# ADE7758.net
KiCad netlist of a schematic drawn in EAGLE
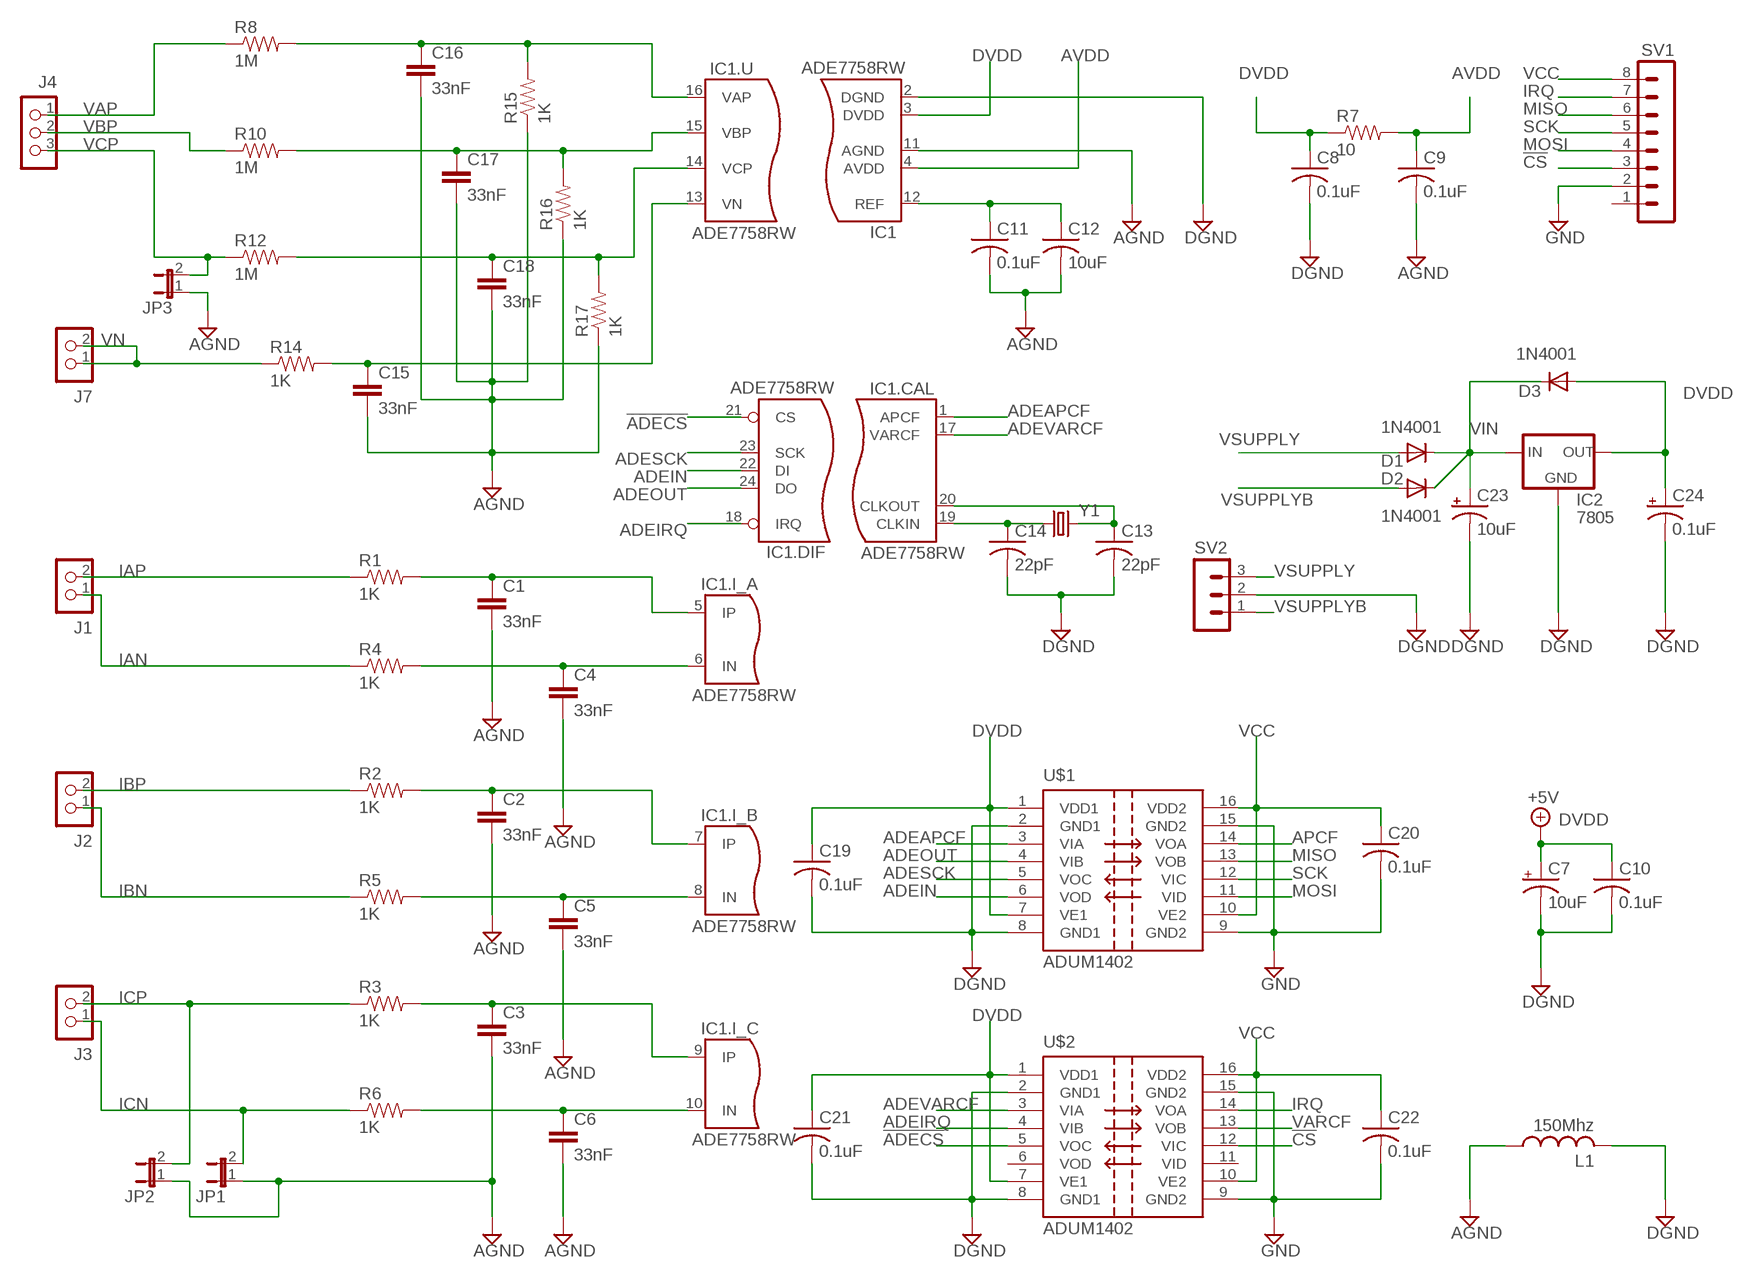
[diagram p0: schematic, sheet 1]

(export (version "E")
  (design (tool "Eeschema 10.0.6"))
  (components
    (comp (ref "C1")
      (value "33nF")
      (footprint "eagle-import:CAP-PTH-SMALL2")
      (libsource (lib "eagle-import") (part "CAPPTH2"))
    )
    (comp (ref "C2")
      (value "33nF")
      (footprint "eagle-import:CAP-PTH-SMALL2")
      (libsource (lib "eagle-import") (part "CAPPTH2"))
    )
    (comp (ref "C3")
      (value "33nF")
      (footprint "eagle-import:CAP-PTH-SMALL2")
      (libsource (lib "eagle-import") (part "CAPPTH2"))
    )
    (comp (ref "C4")
      (value "33nF")
      (footprint "eagle-import:CAP-PTH-SMALL2")
      (libsource (lib "eagle-import") (part "CAPPTH2"))
    )
    (comp (ref "C5")
      (value "33nF")
      (footprint "eagle-import:CAP-PTH-SMALL2")
      (libsource (lib "eagle-import") (part "CAPPTH2"))
    )
    (comp (ref "C6")
      (value "33nF")
      (footprint "eagle-import:CAP-PTH-SMALL2")
      (libsource (lib "eagle-import") (part "CAPPTH2"))
    )
    (comp (ref "C7")
      (value "10uF")
      (footprint "eagle-import:C_6032-28R")
      (libsource (lib "eagle-import") (part "CPOL-USC/6032-28R"))
    )
    (comp (ref "C8")
      (value "0.1uF")
      (footprint "eagle-import:C0805")
      (libsource (lib "eagle-import") (part "C-USC0805"))
    )
    (comp (ref "C9")
      (value "0.1uF")
      (footprint "eagle-import:C0805")
      (libsource (lib "eagle-import") (part "C-USC0805"))
    )
    (comp (ref "C10")
      (value "0.1uF")
      (footprint "eagle-import:C0805")
      (libsource (lib "eagle-import") (part "C-USC0805"))
    )
    (comp (ref "C11")
      (value "0.1uF")
      (footprint "eagle-import:C0805K")
      (libsource (lib "eagle-import") (part "C-USC0805K"))
    )
    (comp (ref "C12")
      (value "10uF")
      (footprint "eagle-import:C0805K")
      (libsource (lib "eagle-import") (part "C-USC0805K"))
    )
    (comp (ref "C13")
      (value "22pF")
      (footprint "eagle-import:C0805K")
      (libsource (lib "eagle-import") (part "C-USC0805K"))
    )
    (comp (ref "C14")
      (value "22pF")
      (footprint "eagle-import:C0805K")
      (libsource (lib "eagle-import") (part "C-USC0805K"))
    )
    (comp (ref "C15")
      (value "33nF")
      (footprint "eagle-import:CAP-PTH-SMALL2")
      (libsource (lib "eagle-import") (part "CAPPTH2"))
    )
    (comp (ref "C16")
      (value "33nF")
      (footprint "eagle-import:CAP-PTH-SMALL2")
      (libsource (lib "eagle-import") (part "CAPPTH2"))
    )
    (comp (ref "C17")
      (value "33nF")
      (footprint "eagle-import:CAP-PTH-SMALL2")
      (libsource (lib "eagle-import") (part "CAPPTH2"))
    )
    (comp (ref "C18")
      (value "33nF")
      (footprint "eagle-import:CAP-PTH-SMALL2")
      (libsource (lib "eagle-import") (part "CAPPTH2"))
    )
    (comp (ref "C19")
      (value "0.1uF")
      (footprint "eagle-import:C0805")
      (libsource (lib "eagle-import") (part "C-USC0805"))
    )
    (comp (ref "C20")
      (value "0.1uF")
      (footprint "eagle-import:C0805")
      (libsource (lib "eagle-import") (part "C-USC0805"))
    )
    (comp (ref "C21")
      (value "0.1uF")
      (footprint "eagle-import:C0805")
      (libsource (lib "eagle-import") (part "C-USC0805"))
    )
    (comp (ref "C22")
      (value "0.1uF")
      (footprint "eagle-import:C0805")
      (libsource (lib "eagle-import") (part "C-USC0805"))
    )
    (comp (ref "C23")
      (value "10uF")
      (footprint "eagle-import:CPOL-RADIAL-100UF-25V")
      (fields (field (name "MPN") "06034D106MAT2A"))
      (libsource (lib "eagle-import") (part "CAP_POLPTH1"))
    )
    (comp (ref "C24")
      (value "0.1uF")
      (footprint "eagle-import:CPOL-RADIAL-10UF-25V")
      (fields (field (name "MPN") "06034D106MAT2A"))
      (libsource (lib "eagle-import") (part "CAP_POLPTH2"))
    )
    (comp (ref "D1")
      (value "1N4001")
      (footprint "eagle-import:D-7.5")
      (libsource (lib "eagle-import") (part "DIODE-D-7.5"))
    )
    (comp (ref "D2")
      (value "1N4001")
      (footprint "eagle-import:D-7.5")
      (libsource (lib "eagle-import") (part "DIODE-D-7.5"))
    )
    (comp (ref "D3")
      (value "1N4001")
      (footprint "eagle-import:D-7.5")
      (libsource (lib "eagle-import") (part "DIODE-D-7.5"))
    )
    (comp (ref "IC1")
      (value "ADE7758RW")
      (footprint "eagle-import:SOIC24")
      (libsource (lib "eagle-import") (part "ADE7758RW"))
    )
    (comp (ref "IC2")
      (value "7805")
      (footprint "eagle-import:78XXS")
      (libsource (lib "eagle-import") (part "78XXS"))
    )
    (comp (ref "J1")
      (value "CON_TERMINAL_BLOCK_02-5MM")
      (footprint "eagle-import:TERMINAL_BLOCK_2P_5")
      (libsource (lib "eagle-import") (part "CON_TERMINAL_BLOCK_02-5MM"))
    )
    (comp (ref "J2")
      (value "CON_TERMINAL_BLOCK_02-5MM")
      (footprint "eagle-import:TERMINAL_BLOCK_2P_5")
      (libsource (lib "eagle-import") (part "CON_TERMINAL_BLOCK_02-5MM"))
    )
    (comp (ref "J3")
      (value "CON_TERMINAL_BLOCK_02-5MM")
      (footprint "eagle-import:TERMINAL_BLOCK_2P_5")
      (libsource (lib "eagle-import") (part "CON_TERMINAL_BLOCK_02-5MM"))
    )
    (comp (ref "J4")
      (value "CON_TERMINAL_BLOCK_03-5MM")
      (footprint "eagle-import:TERMINAL_BLOCK_3P_5")
      (libsource (lib "eagle-import") (part "CON_TERMINAL_BLOCK_03-5MM"))
    )
    (comp (ref "J7")
      (value "CON_TERMINAL_BLOCK_02-5MM")
      (footprint "eagle-import:TERMINAL_BLOCK_2P_5")
      (libsource (lib "eagle-import") (part "CON_TERMINAL_BLOCK_02-5MM"))
    )
    (comp (ref "JP1")
      (value "JP1E")
      (footprint "eagle-import:JP1")
      (libsource (lib "eagle-import") (part "JP1E"))
    )
    (comp (ref "JP2")
      (value "JP1E")
      (footprint "eagle-import:JP1")
      (libsource (lib "eagle-import") (part "JP1E"))
    )
    (comp (ref "JP3")
      (value "JP1E")
      (footprint "eagle-import:JP1")
      (libsource (lib "eagle-import") (part "JP1E"))
    )
    (comp (ref "L1")
      (value "150Mhz")
      (footprint "eagle-import:0207_5V")
      (libsource (lib "eagle-import") (part "L-US0207/5V"))
    )
    (comp (ref "R1")
      (value "1K")
      (footprint "eagle-import:AXIAL-0.4")
      (libsource (lib "eagle-import") (part "RESISTORPTH-1/4W"))
    )
    (comp (ref "R2")
      (value "1K")
      (footprint "eagle-import:AXIAL-0.4")
      (libsource (lib "eagle-import") (part "RESISTORPTH-1/4W"))
    )
    (comp (ref "R3")
      (value "1K")
      (footprint "eagle-import:AXIAL-0.4")
      (libsource (lib "eagle-import") (part "RESISTORPTH-1/4W"))
    )
    (comp (ref "R4")
      (value "1K")
      (footprint "eagle-import:AXIAL-0.4")
      (libsource (lib "eagle-import") (part "RESISTORPTH-1/4W"))
    )
    (comp (ref "R5")
      (value "1K")
      (footprint "eagle-import:AXIAL-0.4")
      (libsource (lib "eagle-import") (part "RESISTORPTH-1/4W"))
    )
    (comp (ref "R6")
      (value "1K")
      (footprint "eagle-import:AXIAL-0.4")
      (libsource (lib "eagle-import") (part "RESISTORPTH-1/4W"))
    )
    (comp (ref "R7")
      (value "10")
      (footprint "eagle-import:AXIAL-0.4")
      (libsource (lib "eagle-import") (part "RESISTORPTH-1/4W"))
    )
    (comp (ref "R8")
      (value "1M")
      (footprint "eagle-import:AXIAL-0.4")
      (libsource (lib "eagle-import") (part "RESISTORPTH-1/4W"))
    )
    (comp (ref "R10")
      (value "1M")
      (footprint "eagle-import:AXIAL-0.4")
      (libsource (lib "eagle-import") (part "RESISTORPTH-1/4W"))
    )
    (comp (ref "R12")
      (value "1M")
      (footprint "eagle-import:AXIAL-0.4")
      (libsource (lib "eagle-import") (part "RESISTORPTH-1/4W"))
    )
    (comp (ref "R14")
      (value "1K")
      (footprint "eagle-import:AXIAL-0.4")
      (libsource (lib "eagle-import") (part "RESISTORPTH-1/4W"))
    )
    (comp (ref "R15")
      (value "1K")
      (footprint "eagle-import:AXIAL-0.4")
      (libsource (lib "eagle-import") (part "RESISTORPTH-1/4W"))
    )
    (comp (ref "R16")
      (value "1K")
      (footprint "eagle-import:AXIAL-0.4")
      (libsource (lib "eagle-import") (part "RESISTORPTH-1/4W"))
    )
    (comp (ref "R17")
      (value "1K")
      (footprint "eagle-import:AXIAL-0.4")
      (libsource (lib "eagle-import") (part "RESISTORPTH-1/4W"))
    )
    (comp (ref "SV1")
      (value "MA08-1")
      (footprint "eagle-import:MA08-1")
      (libsource (lib "eagle-import") (part "MA08-1"))
    )
    (comp (ref "SV2")
      (value "MA03-1")
      (footprint "eagle-import:MA03-1")
      (libsource (lib "eagle-import") (part "MA03-1"))
    )
    (comp (ref "U$1")
      (value "ADUM1402")
      (footprint "eagle-import:SO16W")
      (libsource (lib "eagle-import") (part "ADUM1402"))
    )
    (comp (ref "U$2")
      (value "ADUM1402")
      (footprint "eagle-import:SO16W")
      (libsource (lib "eagle-import") (part "ADUM1402"))
    )
    (comp (ref "Y1")
      (value "CRYSTALHC49US")
      (footprint "eagle-import:HC49US")
      (libsource (lib "eagle-import") (part "CRYSTALHC49US"))
    )
  )
  (nets
    (net (code "1") (name "+5V") (class "Default")
      (node (ref "C10") (pin "1") (pinfunction "1_1") (pintype "passive"))
      (node (ref "C19") (pin "1") (pinfunction "1_1") (pintype "passive"))
      (node (ref "C21") (pin "1") (pinfunction "1_1") (pintype "passive"))
      (node (ref "C24") (pin "1") (pinfunction "+_1") (pintype "passive"))
      (node (ref "C7") (pin "+") (pinfunction "+_+") (pintype "passive"))
      (node (ref "C8") (pin "1") (pinfunction "1_1") (pintype "passive"))
      (node (ref "D3") (pin "A") (pinfunction "A_A") (pintype "passive"))
      (node (ref "IC1") (pin "3") (pinfunction "DVDD_3") (pintype "power_in"))
      (node (ref "IC2") (pin "OUT") (pinfunction "OUT_OUT") (pintype "passive"))
      (node (ref "R7") (pin "P$1") (pinfunction "1_P$1") (pintype "passive"))
      (node (ref "U$1") (pin "1") (pinfunction "VDD1_1") (pintype "power_in"))
      (node (ref "U$1") (pin "7") (pinfunction "VE1_7") (pintype "passive"))
      (node (ref "U$2") (pin "1") (pinfunction "VDD1_1") (pintype "power_in"))
      (node (ref "U$2") (pin "7") (pinfunction "VE1_7") (pintype "passive"))
    )
    (net (code "2") (name "/ADEAPCF") (class "Default")
      (node (ref "IC1") (pin "1") (pinfunction "APCF_1") (pintype "output"))
      (node (ref "U$1") (pin "3") (pinfunction "VIA_3") (pintype "input"))
    )
    (net (code "3") (name "/ADEIN") (class "Default")
      (node (ref "IC1") (pin "22") (pinfunction "DI_22") (pintype "input"))
      (node (ref "U$1") (pin "6") (pinfunction "VOD_6") (pintype "output"))
    )
    (net (code "4") (name "/ADEIRQ") (class "Default")
      (node (ref "IC1") (pin "18") (pinfunction "IRQ_18") (pintype "output"))
      (node (ref "U$2") (pin "4") (pinfunction "VIB_4") (pintype "input"))
    )
    (net (code "5") (name "/ADEOUT") (class "Default")
      (node (ref "IC1") (pin "24") (pinfunction "DO_24") (pintype "output"))
      (node (ref "U$1") (pin "4") (pinfunction "VIB_4") (pintype "input"))
    )
    (net (code "6") (name "/ADESCK") (class "Default")
      (node (ref "IC1") (pin "23") (pinfunction "SCK_23") (pintype "input"))
      (node (ref "U$1") (pin "5") (pinfunction "VOC_5") (pintype "output"))
    )
    (net (code "7") (name "/ADEVARCF") (class "Default")
      (node (ref "IC1") (pin "17") (pinfunction "VARCF_17") (pintype "output"))
      (node (ref "U$2") (pin "3") (pinfunction "VIA_3") (pintype "input"))
    )
    (net (code "8") (name "/APCF") (class "Default")
      (node (ref "U$1") (pin "14") (pinfunction "VOA_14") (pintype "output"))
    )
    (net (code "9") (name "/AVDD") (class "Default")
      (node (ref "C9") (pin "1") (pinfunction "1_1") (pintype "passive"))
      (node (ref "IC1") (pin "4") (pinfunction "AVDD_4") (pintype "power_in"))
      (node (ref "R7") (pin "P$2") (pinfunction "2_P$2") (pintype "passive"))
    )
    (net (code "10") (name "/IAN") (class "Default")
      (node (ref "J1") (pin "1") (pinfunction "1_1") (pintype "passive"))
      (node (ref "R4") (pin "P$1") (pinfunction "1_P$1") (pintype "passive"))
    )
    (net (code "11") (name "/IAP") (class "Default")
      (node (ref "J1") (pin "2") (pinfunction "2_2") (pintype "passive"))
      (node (ref "R1") (pin "P$1") (pinfunction "1_P$1") (pintype "passive"))
    )
    (net (code "12") (name "/IBN") (class "Default")
      (node (ref "J2") (pin "1") (pinfunction "1_1") (pintype "passive"))
      (node (ref "R5") (pin "P$1") (pinfunction "1_P$1") (pintype "passive"))
    )
    (net (code "13") (name "/IBP") (class "Default")
      (node (ref "J2") (pin "2") (pinfunction "2_2") (pintype "passive"))
      (node (ref "R2") (pin "P$1") (pinfunction "1_P$1") (pintype "passive"))
    )
    (net (code "14") (name "/ICN") (class "Default")
      (node (ref "J3") (pin "1") (pinfunction "1_1") (pintype "passive"))
      (node (ref "JP1") (pin "2") (pinfunction "2_2") (pintype "passive"))
      (node (ref "R6") (pin "P$1") (pinfunction "1_P$1") (pintype "passive"))
    )
    (net (code "15") (name "/ICP") (class "Default")
      (node (ref "J3") (pin "2") (pinfunction "2_2") (pintype "passive"))
      (node (ref "JP2") (pin "2") (pinfunction "2_2") (pintype "passive"))
      (node (ref "R3") (pin "P$1") (pinfunction "1_P$1") (pintype "passive"))
    )
    (net (code "16") (name "/IRQ") (class "Default")
      (node (ref "SV1") (pin "7") (pinfunction "7_7") (pintype "passive"))
      (node (ref "U$2") (pin "14") (pinfunction "VOA_14") (pintype "output"))
    )
    (net (code "17") (name "/MISO") (class "Default")
      (node (ref "SV1") (pin "6") (pinfunction "6_6") (pintype "passive"))
      (node (ref "U$1") (pin "13") (pinfunction "VOB_13") (pintype "output"))
    )
    (net (code "18") (name "/MOSI") (class "Default")
      (node (ref "SV1") (pin "4") (pinfunction "4_4") (pintype "passive"))
      (node (ref "U$1") (pin "11") (pinfunction "VID_11") (pintype "input"))
    )
    (net (code "19") (name "/SCK") (class "Default")
      (node (ref "SV1") (pin "5") (pinfunction "5_5") (pintype "passive"))
      (node (ref "U$1") (pin "12") (pinfunction "VIC_12") (pintype "input"))
    )
    (net (code "20") (name "/VAP") (class "Default")
      (node (ref "J4") (pin "1") (pinfunction "1_1") (pintype "bidirectional"))
      (node (ref "R8") (pin "P$1") (pinfunction "1_P$1") (pintype "passive"))
    )
    (net (code "21") (name "/VARCF") (class "Default")
      (node (ref "U$2") (pin "13") (pinfunction "VOB_13") (pintype "output"))
    )
    (net (code "22") (name "/VBP") (class "Default")
      (node (ref "J4") (pin "2") (pinfunction "2_2") (pintype "bidirectional"))
      (node (ref "R10") (pin "P$1") (pinfunction "1_P$1") (pintype "passive"))
    )
    (net (code "23") (name "/VCC") (class "Default")
      (node (ref "C20") (pin "1") (pinfunction "1_1") (pintype "passive"))
      (node (ref "C22") (pin "1") (pinfunction "1_1") (pintype "passive"))
      (node (ref "SV1") (pin "8") (pinfunction "8_8") (pintype "passive"))
      (node (ref "U$1") (pin "10") (pinfunction "VE2_10") (pintype "passive"))
      (node (ref "U$1") (pin "16") (pinfunction "VDD2_16") (pintype "power_in"))
      (node (ref "U$2") (pin "10") (pinfunction "VE2_10") (pintype "passive"))
      (node (ref "U$2") (pin "16") (pinfunction "VDD2_16") (pintype "power_in"))
    )
    (net (code "24") (name "/VCP") (class "Default")
      (node (ref "J4") (pin "3") (pinfunction "3_3") (pintype "bidirectional"))
      (node (ref "JP3") (pin "2") (pinfunction "2_2") (pintype "passive"))
      (node (ref "R12") (pin "P$1") (pinfunction "1_P$1") (pintype "passive"))
    )
    (net (code "25") (name "/VIN") (class "Default")
      (node (ref "C23") (pin "1") (pinfunction "+_1") (pintype "passive"))
      (node (ref "D1") (pin "C") (pinfunction "C_C") (pintype "passive"))
      (node (ref "D2") (pin "C") (pinfunction "C_C") (pintype "passive"))
      (node (ref "D3") (pin "C") (pinfunction "C_C") (pintype "passive"))
      (node (ref "IC2") (pin "IN") (pinfunction "IN_IN") (pintype "input"))
    )
    (net (code "26") (name "/VN") (class "Default")
      (node (ref "J7") (pin "1") (pinfunction "1_1") (pintype "passive"))
      (node (ref "J7") (pin "2") (pinfunction "2_2") (pintype "passive"))
      (node (ref "R14") (pin "P$1") (pinfunction "1_P$1") (pintype "passive"))
    )
    (net (code "27") (name "/VSUPPLY") (class "Default")
      (node (ref "D1") (pin "A") (pinfunction "A_A") (pintype "passive"))
      (node (ref "SV2") (pin "3") (pinfunction "3_3") (pintype "passive"))
    )
    (net (code "28") (name "/VSUPPLYB") (class "Default")
      (node (ref "D2") (pin "A") (pinfunction "A_A") (pintype "passive"))
      (node (ref "SV2") (pin "1") (pinfunction "1_1") (pintype "passive"))
    )
    (net (code "29") (name "/~{ADECS}") (class "Default")
      (node (ref "IC1") (pin "21") (pinfunction "CS_21") (pintype "input"))
      (node (ref "U$2") (pin "5") (pinfunction "VOC_5") (pintype "output"))
    )
    (net (code "30") (name "/~{CS}") (class "Default")
      (node (ref "SV1") (pin "3") (pinfunction "3_3") (pintype "passive"))
      (node (ref "U$2") (pin "12") (pinfunction "VIC_12") (pintype "input"))
    )
    (net (code "31") (name "AGND") (class "Default")
      (node (ref "C1") (pin "2") (pinfunction "2_2") (pintype "passive"))
      (node (ref "C11") (pin "2") (pinfunction "2_2") (pintype "passive"))
      (node (ref "C12") (pin "2") (pinfunction "2_2") (pintype "passive"))
      (node (ref "C15") (pin "2") (pinfunction "2_2") (pintype "passive"))
      (node (ref "C16") (pin "2") (pinfunction "2_2") (pintype "passive"))
      (node (ref "C17") (pin "2") (pinfunction "2_2") (pintype "passive"))
      (node (ref "C18") (pin "2") (pinfunction "2_2") (pintype "passive"))
      (node (ref "C2") (pin "2") (pinfunction "2_2") (pintype "passive"))
      (node (ref "C3") (pin "2") (pinfunction "2_2") (pintype "passive"))
      (node (ref "C4") (pin "2") (pinfunction "2_2") (pintype "passive"))
      (node (ref "C5") (pin "2") (pinfunction "2_2") (pintype "passive"))
      (node (ref "C6") (pin "2") (pinfunction "2_2") (pintype "passive"))
      (node (ref "C9") (pin "2") (pinfunction "2_2") (pintype "passive"))
      (node (ref "IC1") (pin "11") (pinfunction "AGND_11") (pintype "power_in"))
      (node (ref "JP1") (pin "1") (pinfunction "1_1") (pintype "passive"))
      (node (ref "JP2") (pin "1") (pinfunction "1_1") (pintype "passive"))
      (node (ref "JP3") (pin "1") (pinfunction "1_1") (pintype "passive"))
      (node (ref "L1") (pin "1") (pinfunction "1_1") (pintype "passive"))
      (node (ref "R15") (pin "P$1") (pinfunction "1_P$1") (pintype "passive"))
      (node (ref "R16") (pin "P$1") (pinfunction "1_P$1") (pintype "passive"))
      (node (ref "R17") (pin "P$1") (pinfunction "1_P$1") (pintype "passive"))
    )
    (net (code "32") (name "DGND") (class "Default")
      (node (ref "C10") (pin "2") (pinfunction "2_2") (pintype "passive"))
      (node (ref "C13") (pin "2") (pinfunction "2_2") (pintype "passive"))
      (node (ref "C14") (pin "2") (pinfunction "2_2") (pintype "passive"))
      (node (ref "C19") (pin "2") (pinfunction "2_2") (pintype "passive"))
      (node (ref "C21") (pin "2") (pinfunction "2_2") (pintype "passive"))
      (node (ref "C23") (pin "2") (pinfunction "-_2") (pintype "passive"))
      (node (ref "C24") (pin "2") (pinfunction "-_2") (pintype "passive"))
      (node (ref "C7") (pin "-") (pinfunction "-_-") (pintype "passive"))
      (node (ref "C8") (pin "2") (pinfunction "2_2") (pintype "passive"))
      (node (ref "IC1") (pin "2") (pinfunction "DGND_2") (pintype "power_in"))
      (node (ref "IC2") (pin "GND") (pinfunction "GND_GND") (pintype "input"))
      (node (ref "L1") (pin "2") (pinfunction "2_2") (pintype "passive"))
      (node (ref "SV2") (pin "2") (pinfunction "2_2") (pintype "passive"))
      (node (ref "U$1") (pin "2") (pinfunction "GND1_2") (pintype "power_in"))
      (node (ref "U$1") (pin "8") (pinfunction "GND1_8") (pintype "power_in"))
      (node (ref "U$2") (pin "2") (pinfunction "GND1_2") (pintype "power_in"))
      (node (ref "U$2") (pin "8") (pinfunction "GND1_8") (pintype "power_in"))
    )
    (net (code "33") (name "GND") (class "Default")
      (node (ref "C20") (pin "2") (pinfunction "2_2") (pintype "passive"))
      (node (ref "C22") (pin "2") (pinfunction "2_2") (pintype "passive"))
      (node (ref "SV1") (pin "2") (pinfunction "2_2") (pintype "passive"))
      (node (ref "U$1") (pin "15") (pinfunction "GND2_15") (pintype "power_in"))
      (node (ref "U$1") (pin "9") (pinfunction "GND2_9") (pintype "power_in"))
      (node (ref "U$2") (pin "15") (pinfunction "GND2_15") (pintype "power_in"))
      (node (ref "U$2") (pin "9") (pinfunction "GND2_9") (pintype "power_in"))
    )
    (net (code "34") (name "Net-(IC1A-CLKIN)") (class "Default")
      (node (ref "C14") (pin "1") (pinfunction "1_1") (pintype "passive"))
      (node (ref "IC1") (pin "19") (pinfunction "CLKIN_19") (pintype "input"))
      (node (ref "Y1") (pin "1") (pinfunction "1_1") (pintype "passive"))
    )
    (net (code "35") (name "Net-(IC1A-CLKOUT)") (class "Default")
      (node (ref "C13") (pin "1") (pinfunction "1_1") (pintype "passive"))
      (node (ref "IC1") (pin "20") (pinfunction "CLKOUT_20") (pintype "output"))
      (node (ref "Y1") (pin "2") (pinfunction "2_2") (pintype "passive"))
    )
    (net (code "36") (name "Net-(IC1C-IN)") (class "Default")
      (node (ref "C4") (pin "1") (pinfunction "1_1") (pintype "passive"))
      (node (ref "IC1") (pin "6") (pinfunction "IN_6") (pintype "input"))
      (node (ref "R4") (pin "P$2") (pinfunction "2_P$2") (pintype "passive"))
    )
    (net (code "37") (name "Net-(IC1C-IP)") (class "Default")
      (node (ref "C1") (pin "1") (pinfunction "1_1") (pintype "passive"))
      (node (ref "IC1") (pin "5") (pinfunction "IP_5") (pintype "input"))
      (node (ref "R1") (pin "P$2") (pinfunction "2_P$2") (pintype "passive"))
    )
    (net (code "38") (name "Net-(IC1D-IN)") (class "Default")
      (node (ref "C5") (pin "1") (pinfunction "1_1") (pintype "passive"))
      (node (ref "IC1") (pin "8") (pinfunction "IN_8") (pintype "input"))
      (node (ref "R5") (pin "P$2") (pinfunction "2_P$2") (pintype "passive"))
    )
    (net (code "39") (name "Net-(IC1D-IP)") (class "Default")
      (node (ref "C2") (pin "1") (pinfunction "1_1") (pintype "passive"))
      (node (ref "IC1") (pin "7") (pinfunction "IP_7") (pintype "input"))
      (node (ref "R2") (pin "P$2") (pinfunction "2_P$2") (pintype "passive"))
    )
    (net (code "40") (name "Net-(IC1E-IN)") (class "Default")
      (node (ref "C6") (pin "1") (pinfunction "1_1") (pintype "passive"))
      (node (ref "IC1") (pin "10") (pinfunction "IN_10") (pintype "input"))
      (node (ref "R6") (pin "P$2") (pinfunction "2_P$2") (pintype "passive"))
    )
    (net (code "41") (name "Net-(IC1E-IP)") (class "Default")
      (node (ref "C3") (pin "1") (pinfunction "1_1") (pintype "passive"))
      (node (ref "IC1") (pin "9") (pinfunction "IP_9") (pintype "input"))
      (node (ref "R3") (pin "P$2") (pinfunction "2_P$2") (pintype "passive"))
    )
    (net (code "42") (name "Net-(IC1F-REF)") (class "Default")
      (node (ref "C11") (pin "1") (pinfunction "1_1") (pintype "passive"))
      (node (ref "C12") (pin "1") (pinfunction "1_1") (pintype "passive"))
      (node (ref "IC1") (pin "12") (pinfunction "REF_12") (pintype "bidirectional"))
    )
    (net (code "43") (name "Net-(IC1G-VAP)") (class "Default")
      (node (ref "C16") (pin "1") (pinfunction "1_1") (pintype "passive"))
      (node (ref "IC1") (pin "16") (pinfunction "VAP_16") (pintype "input"))
      (node (ref "R15") (pin "P$2") (pinfunction "2_P$2") (pintype "passive"))
      (node (ref "R8") (pin "P$2") (pinfunction "2_P$2") (pintype "passive"))
    )
    (net (code "44") (name "Net-(IC1G-VBP)") (class "Default")
      (node (ref "C17") (pin "1") (pinfunction "1_1") (pintype "passive"))
      (node (ref "IC1") (pin "15") (pinfunction "VBP_15") (pintype "input"))
      (node (ref "R10") (pin "P$2") (pinfunction "2_P$2") (pintype "passive"))
      (node (ref "R16") (pin "P$2") (pinfunction "2_P$2") (pintype "passive"))
    )
    (net (code "45") (name "Net-(IC1G-VCP)") (class "Default")
      (node (ref "C18") (pin "1") (pinfunction "1_1") (pintype "passive"))
      (node (ref "IC1") (pin "14") (pinfunction "VCP_14") (pintype "input"))
      (node (ref "R12") (pin "P$2") (pinfunction "2_P$2") (pintype "passive"))
      (node (ref "R17") (pin "P$2") (pinfunction "2_P$2") (pintype "passive"))
    )
    (net (code "46") (name "Net-(IC1G-VN)") (class "Default")
      (node (ref "C15") (pin "1") (pinfunction "1_1") (pintype "passive"))
      (node (ref "IC1") (pin "13") (pinfunction "VN_13") (pintype "input"))
      (node (ref "R14") (pin "P$2") (pinfunction "2_P$2") (pintype "passive"))
    )
    (net (code "47") (name "unconnected-(SV1-Pad1)") (class "Default")
      (node (ref "SV1") (pin "1") (pinfunction "1_1") (pintype "passive"))
    )
    (net (code "48") (name "unconnected-(U$2-VID-Pad11)") (class "Default")
      (node (ref "U$2") (pin "11") (pinfunction "VID_11") (pintype "input"))
    )
    (net (code "49") (name "unconnected-(U$2-VOD-Pad6)") (class "Default")
      (node (ref "U$2") (pin "6") (pinfunction "VOD_6") (pintype "output"))
    )
  )
)
